# MicroBit_Robot_Interface_RevC.net
KiCad netlist of a schematic drawn in EAGLE
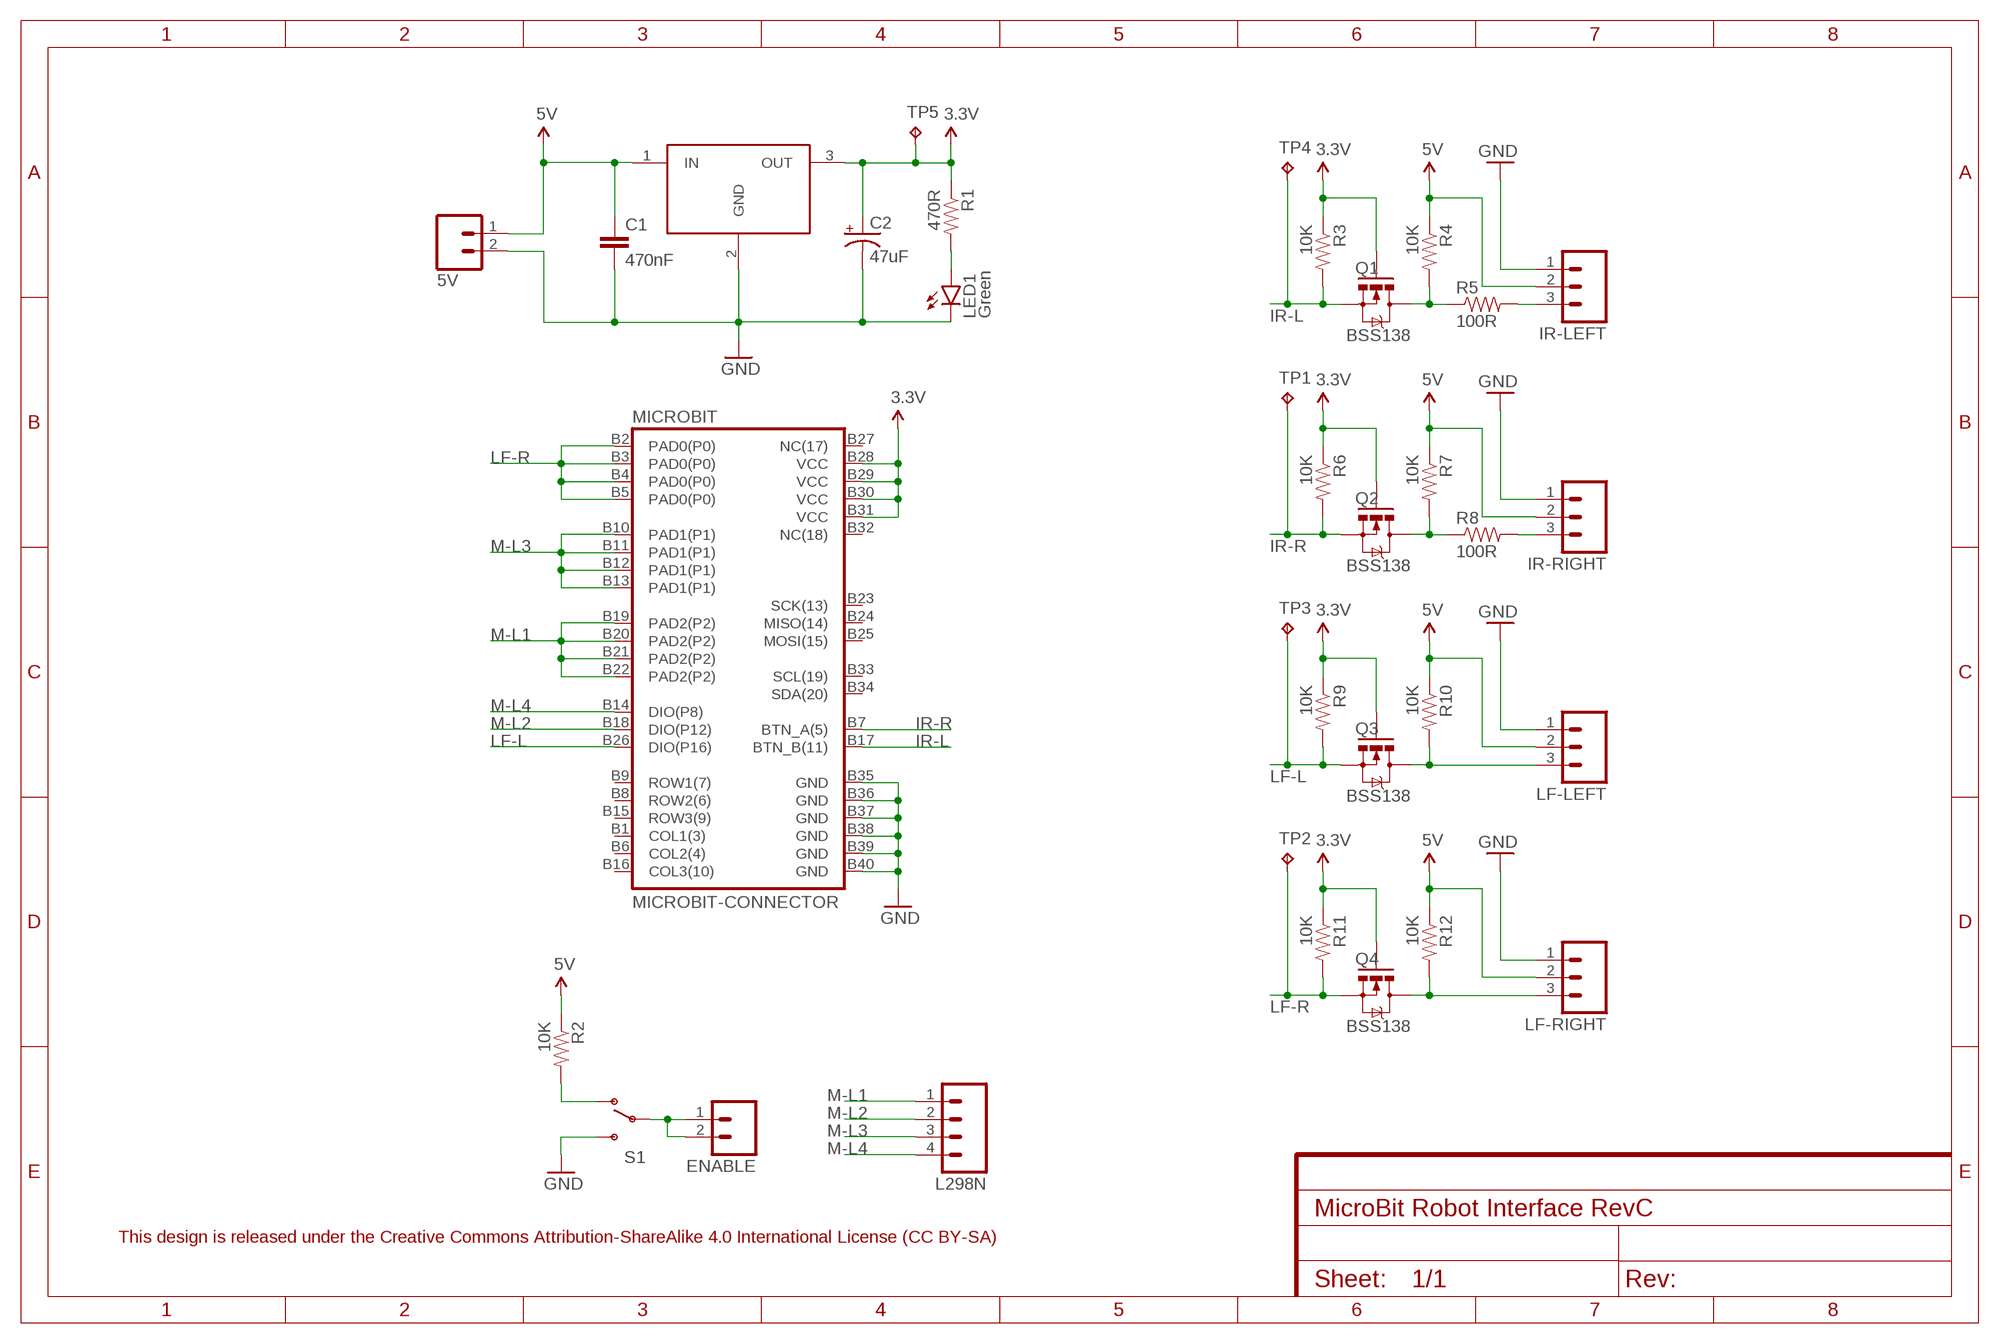
[diagram p0: schematic, sheet 1]

(export (version "E")
  (design (tool "Eeschema 10.0.6"))
  (components
    (comp (ref "5V")
      (value "MCOMP_SCREWTERM_2PIN5MM")
      (footprint "eagle-import:MCOMP-SCREWTERMINAL-5MM-2")
      (libsource (lib "eagle-import") (part "MCOMP_SCREWTERM_2PIN5MM"))
    )
    (comp (ref "C1")
      (value "470nF")
      (footprint "eagle-import:0603-CAP")
      (libsource (lib "eagle-import") (part "CAP0603-CAP"))
    )
    (comp (ref "C2")
      (value "47uF")
      (footprint "eagle-import:CPOL-RADIAL-100UF-25V")
      (libsource (lib "eagle-import") (part "CAP_POLPTH1"))
    )
    (comp (ref "ENABLE")
      (value "M02PTH")
      (footprint "eagle-import:1X02")
      (libsource (lib "eagle-import") (part "M02PTH"))
    )
    (comp (ref "IR-LEFT")
      (value "M03PTH")
      (footprint "eagle-import:1X03")
      (libsource (lib "eagle-import") (part "M03PTH"))
    )
    (comp (ref "IR-RIGHT")
      (value "M03PTH")
      (footprint "eagle-import:1X03")
      (libsource (lib "eagle-import") (part "M03PTH"))
    )
    (comp (ref "L298N")
      (value "M04PTH")
      (footprint "eagle-import:1X04")
      (libsource (lib "eagle-import") (part "M04PTH"))
    )
    (comp (ref "LED1")
      (value "Green")
      (footprint "eagle-import:LED3MM")
      (libsource (lib "eagle-import") (part "LED3MM"))
    )
    (comp (ref "LF-LEFT")
      (value "M03PTH")
      (footprint "eagle-import:1X03")
      (libsource (lib "eagle-import") (part "M03PTH"))
    )
    (comp (ref "LF-RIGHT")
      (value "M03PTH")
      (footprint "eagle-import:1X03")
      (libsource (lib "eagle-import") (part "M03PTH"))
    )
    (comp (ref "MICROBIT")
      (value "MICROBIT-CONNECTOR")
      (footprint "eagle-import:RBB40DHHN_MICROBIT")
      (libsource (lib "eagle-import") (part "MICROBIT-CONNECTOR"))
    )
    (comp (ref "Q1")
      (value "BSS138")
      (footprint "eagle-import:SOT23-3")
      (libsource (lib "eagle-import") (part "MOSFET-NCHANNELBSS138"))
    )
    (comp (ref "Q2")
      (value "BSS138")
      (footprint "eagle-import:SOT23-3")
      (libsource (lib "eagle-import") (part "MOSFET-NCHANNELBSS138"))
    )
    (comp (ref "Q3")
      (value "BSS138")
      (footprint "eagle-import:SOT23-3")
      (libsource (lib "eagle-import") (part "MOSFET-NCHANNELBSS138"))
    )
    (comp (ref "Q4")
      (value "BSS138")
      (footprint "eagle-import:SOT23-3")
      (libsource (lib "eagle-import") (part "MOSFET-NCHANNELBSS138"))
    )
    (comp (ref "R1")
      (value "470R")
      (footprint "eagle-import:0603-RES")
      (libsource (lib "eagle-import") (part "RESISTOR0603-RES"))
    )
    (comp (ref "R2")
      (value "10K")
      (footprint "eagle-import:0603-RES")
      (libsource (lib "eagle-import") (part "RESISTOR0603-RES"))
    )
    (comp (ref "R3")
      (value "10K")
      (footprint "eagle-import:0603-RES")
      (libsource (lib "eagle-import") (part "RESISTOR0603-RES"))
    )
    (comp (ref "R4")
      (value "10K")
      (footprint "eagle-import:0603-RES")
      (libsource (lib "eagle-import") (part "RESISTOR0603-RES"))
    )
    (comp (ref "R5")
      (value "100R")
      (footprint "eagle-import:0603-RES")
      (libsource (lib "eagle-import") (part "RESISTOR0603-RES"))
    )
    (comp (ref "R6")
      (value "10K")
      (footprint "eagle-import:0603-RES")
      (libsource (lib "eagle-import") (part "RESISTOR0603-RES"))
    )
    (comp (ref "R7")
      (value "10K")
      (footprint "eagle-import:0603-RES")
      (libsource (lib "eagle-import") (part "RESISTOR0603-RES"))
    )
    (comp (ref "R8")
      (value "100R")
      (footprint "eagle-import:0603-RES")
      (libsource (lib "eagle-import") (part "RESISTOR0603-RES"))
    )
    (comp (ref "R9")
      (value "10K")
      (footprint "eagle-import:0603-RES")
      (libsource (lib "eagle-import") (part "RESISTOR0603-RES"))
    )
    (comp (ref "R10")
      (value "10K")
      (footprint "eagle-import:0603-RES")
      (libsource (lib "eagle-import") (part "RESISTOR0603-RES"))
    )
    (comp (ref "R11")
      (value "10K")
      (footprint "eagle-import:0603-RES")
      (libsource (lib "eagle-import") (part "RESISTOR0603-RES"))
    )
    (comp (ref "R12")
      (value "10K")
      (footprint "eagle-import:0603-RES")
      (libsource (lib "eagle-import") (part "RESISTOR0603-RES"))
    )
    (comp (ref "S1")
      (value "KNITTER-SWITCH-MFP106D")
      (footprint "eagle-import:KNITTER-SWITCH-MFP106D")
      (libsource (lib "eagle-import") (part "KNITTER-SWITCH-MFP106D"))
    )
    (comp (ref "TP1")
      (value "TPTP10R")
      (footprint "eagle-import:TP10R")
      (libsource (lib "eagle-import") (part "TPTP10R"))
    )
    (comp (ref "TP2")
      (value "TPTP10R")
      (footprint "eagle-import:TP10R")
      (libsource (lib "eagle-import") (part "TPTP10R"))
    )
    (comp (ref "TP3")
      (value "TPTP10R")
      (footprint "eagle-import:TP10R")
      (libsource (lib "eagle-import") (part "TPTP10R"))
    )
    (comp (ref "TP4")
      (value "TPTP10R")
      (footprint "eagle-import:TP10R")
      (libsource (lib "eagle-import") (part "TPTP10R"))
    )
    (comp (ref "TP5")
      (value "TPTP10R")
      (footprint "eagle-import:TP10R")
      (libsource (lib "eagle-import") (part "TPTP10R"))
    )
    (comp (ref "VR1")
      (value "LM3940IMP-3.3")
      (footprint "eagle-import:SOT223")
      (libsource (lib "eagle-import") (part "LM3940IMP-3.3"))
    )
  )
  (nets
    (net (code "1") (name "/IR-L") (class "Default")
      (node (ref "MICROBIT") (pin "B17") (pinfunction "BTN_B(11)_B17") (pintype "input"))
      (node (ref "Q1") (pin "2") (pinfunction "S_2") (pintype "passive"))
      (node (ref "R3") (pin "2") (pinfunction "2_2") (pintype "passive"))
      (node (ref "TP4") (pin "TP") (pinfunction "TP_TP") (pintype "input"))
    )
    (net (code "2") (name "/IR-R") (class "Default")
      (node (ref "MICROBIT") (pin "B7") (pinfunction "BTN_A(5)_B7") (pintype "input"))
      (node (ref "Q2") (pin "2") (pinfunction "S_2") (pintype "passive"))
      (node (ref "R6") (pin "2") (pinfunction "2_2") (pintype "passive"))
      (node (ref "TP1") (pin "TP") (pinfunction "TP_TP") (pintype "input"))
    )
    (net (code "3") (name "/LF-L") (class "Default")
      (node (ref "MICROBIT") (pin "B26") (pinfunction "DIO(P16)_B26") (pintype "bidirectional"))
      (node (ref "Q3") (pin "2") (pinfunction "S_2") (pintype "passive"))
      (node (ref "R9") (pin "2") (pinfunction "2_2") (pintype "passive"))
      (node (ref "TP3") (pin "TP") (pinfunction "TP_TP") (pintype "input"))
    )
    (net (code "4") (name "/LF-R") (class "Default")
      (node (ref "MICROBIT") (pin "B2") (pinfunction "PAD0(P0)_B2") (pintype "bidirectional"))
      (node (ref "MICROBIT") (pin "B3") (pinfunction "PAD0(P0)_B3") (pintype "bidirectional"))
      (node (ref "MICROBIT") (pin "B4") (pinfunction "PAD0(P0)_B4") (pintype "bidirectional"))
      (node (ref "MICROBIT") (pin "B5") (pinfunction "PAD0(P0)_B5") (pintype "bidirectional"))
      (node (ref "Q4") (pin "2") (pinfunction "S_2") (pintype "passive"))
      (node (ref "R11") (pin "2") (pinfunction "2_2") (pintype "passive"))
      (node (ref "TP2") (pin "TP") (pinfunction "TP_TP") (pintype "input"))
    )
    (net (code "5") (name "/M-L1") (class "Default")
      (node (ref "L298N") (pin "1") (pinfunction "1_1") (pintype "passive"))
      (node (ref "MICROBIT") (pin "B19") (pinfunction "PAD2(P2)_B19") (pintype "bidirectional"))
      (node (ref "MICROBIT") (pin "B20") (pinfunction "PAD2(P2)_B20") (pintype "bidirectional"))
      (node (ref "MICROBIT") (pin "B21") (pinfunction "PAD2(P2)_B21") (pintype "bidirectional"))
      (node (ref "MICROBIT") (pin "B22") (pinfunction "PAD2(P2)_B22") (pintype "bidirectional"))
    )
    (net (code "6") (name "/M-L2") (class "Default")
      (node (ref "L298N") (pin "2") (pinfunction "2_2") (pintype "passive"))
      (node (ref "MICROBIT") (pin "B18") (pinfunction "DIO(P12)_B18") (pintype "bidirectional"))
    )
    (net (code "7") (name "/M-L3") (class "Default")
      (node (ref "L298N") (pin "3") (pinfunction "3_3") (pintype "passive"))
      (node (ref "MICROBIT") (pin "B10") (pinfunction "PAD1(P1)_B10") (pintype "bidirectional"))
      (node (ref "MICROBIT") (pin "B11") (pinfunction "PAD1(P1)_B11") (pintype "bidirectional"))
      (node (ref "MICROBIT") (pin "B12") (pinfunction "PAD1(P1)_B12") (pintype "bidirectional"))
      (node (ref "MICROBIT") (pin "B13") (pinfunction "PAD1(P1)_B13") (pintype "bidirectional"))
    )
    (net (code "8") (name "/M-L4") (class "Default")
      (node (ref "L298N") (pin "4") (pinfunction "4_4") (pintype "passive"))
      (node (ref "MICROBIT") (pin "B14") (pinfunction "DIO(P8)_B14") (pintype "bidirectional"))
    )
    (net (code "9") (name "3.3V") (class "Default")
      (node (ref "C2") (pin "1") (pinfunction "+_1") (pintype "passive"))
      (node (ref "MICROBIT") (pin "B28") (pinfunction "VCC_B28") (pintype "power_in"))
      (node (ref "MICROBIT") (pin "B29") (pinfunction "VCC_B29") (pintype "power_in"))
      (node (ref "MICROBIT") (pin "B30") (pinfunction "VCC_B30") (pintype "power_in"))
      (node (ref "MICROBIT") (pin "B31") (pinfunction "VCC_B31") (pintype "power_in"))
      (node (ref "Q1") (pin "1") (pinfunction "G_1") (pintype "passive"))
      (node (ref "Q2") (pin "1") (pinfunction "G_1") (pintype "passive"))
      (node (ref "Q3") (pin "1") (pinfunction "G_1") (pintype "passive"))
      (node (ref "Q4") (pin "1") (pinfunction "G_1") (pintype "passive"))
      (node (ref "R1") (pin "1") (pinfunction "1_1") (pintype "passive"))
      (node (ref "R11") (pin "1") (pinfunction "1_1") (pintype "passive"))
      (node (ref "R3") (pin "1") (pinfunction "1_1") (pintype "passive"))
      (node (ref "R6") (pin "1") (pinfunction "1_1") (pintype "passive"))
      (node (ref "R9") (pin "1") (pinfunction "1_1") (pintype "passive"))
      (node (ref "TP5") (pin "TP") (pinfunction "TP_TP") (pintype "input"))
      (node (ref "VR1") (pin "3") (pinfunction "OUT_3") (pintype "power_in"))
    )
    (net (code "10") (name "5V") (class "Default")
      (node (ref "5V") (pin "1") (pinfunction "1_1") (pintype "passive"))
      (node (ref "C1") (pin "1") (pinfunction "1_1") (pintype "passive"))
      (node (ref "IR-LEFT") (pin "2") (pinfunction "2_2") (pintype "passive"))
      (node (ref "IR-RIGHT") (pin "2") (pinfunction "2_2") (pintype "passive"))
      (node (ref "LF-LEFT") (pin "2") (pinfunction "2_2") (pintype "passive"))
      (node (ref "LF-RIGHT") (pin "2") (pinfunction "2_2") (pintype "passive"))
      (node (ref "R10") (pin "1") (pinfunction "1_1") (pintype "passive"))
      (node (ref "R12") (pin "1") (pinfunction "1_1") (pintype "passive"))
      (node (ref "R2") (pin "1") (pinfunction "1_1") (pintype "passive"))
      (node (ref "R4") (pin "1") (pinfunction "1_1") (pintype "passive"))
      (node (ref "R7") (pin "1") (pinfunction "1_1") (pintype "passive"))
      (node (ref "VR1") (pin "1") (pinfunction "IN_1") (pintype "power_in"))
    )
    (net (code "11") (name "GND") (class "Default")
      (node (ref "5V") (pin "2") (pinfunction "2_2") (pintype "passive"))
      (node (ref "C1") (pin "2") (pinfunction "2_2") (pintype "passive"))
      (node (ref "C2") (pin "2") (pinfunction "-_2") (pintype "passive"))
      (node (ref "IR-LEFT") (pin "1") (pinfunction "1_1") (pintype "passive"))
      (node (ref "IR-RIGHT") (pin "1") (pinfunction "1_1") (pintype "passive"))
      (node (ref "LED1") (pin "K") (pinfunction "C_K") (pintype "passive"))
      (node (ref "LF-LEFT") (pin "1") (pinfunction "1_1") (pintype "passive"))
      (node (ref "LF-RIGHT") (pin "1") (pinfunction "1_1") (pintype "passive"))
      (node (ref "MICROBIT") (pin "B35") (pinfunction "GND_B35") (pintype "power_in"))
      (node (ref "MICROBIT") (pin "B36") (pinfunction "GND_B36") (pintype "power_in"))
      (node (ref "MICROBIT") (pin "B37") (pinfunction "GND_B37") (pintype "power_in"))
      (node (ref "MICROBIT") (pin "B38") (pinfunction "GND_B38") (pintype "power_in"))
      (node (ref "MICROBIT") (pin "B39") (pinfunction "GND_B39") (pintype "power_in"))
      (node (ref "MICROBIT") (pin "B40") (pinfunction "GND_B40") (pintype "power_in"))
      (node (ref "S1") (pin "P$2") (pinfunction "POS2_P$2") (pintype "passive"))
      (node (ref "VR1") (pin "2") (pinfunction "GND_2") (pintype "power_in"))
    )
    (net (code "12") (name "Net-(IR-LEFT-Pad3)") (class "Default")
      (node (ref "IR-LEFT") (pin "3") (pinfunction "3_3") (pintype "passive"))
      (node (ref "R5") (pin "2") (pinfunction "2_2") (pintype "passive"))
    )
    (net (code "13") (name "Net-(IR-RIGHT-Pad3)") (class "Default")
      (node (ref "IR-RIGHT") (pin "3") (pinfunction "3_3") (pintype "passive"))
      (node (ref "R8") (pin "2") (pinfunction "2_2") (pintype "passive"))
    )
    (net (code "14") (name "Net-(LED1-PadA)") (class "Default")
      (node (ref "LED1") (pin "A") (pinfunction "A_A") (pintype "passive"))
      (node (ref "R1") (pin "2") (pinfunction "2_2") (pintype "passive"))
    )
    (net (code "15") (name "Net-(Q1-D)") (class "Default")
      (node (ref "Q1") (pin "3") (pinfunction "D_3") (pintype "passive"))
      (node (ref "R4") (pin "2") (pinfunction "2_2") (pintype "passive"))
      (node (ref "R5") (pin "1") (pinfunction "1_1") (pintype "passive"))
    )
    (net (code "16") (name "Net-(Q2-D)") (class "Default")
      (node (ref "Q2") (pin "3") (pinfunction "D_3") (pintype "passive"))
      (node (ref "R7") (pin "2") (pinfunction "2_2") (pintype "passive"))
      (node (ref "R8") (pin "1") (pinfunction "1_1") (pintype "passive"))
    )
    (net (code "17") (name "Net-(Q3-D)") (class "Default")
      (node (ref "LF-LEFT") (pin "3") (pinfunction "3_3") (pintype "passive"))
      (node (ref "Q3") (pin "3") (pinfunction "D_3") (pintype "passive"))
      (node (ref "R10") (pin "2") (pinfunction "2_2") (pintype "passive"))
    )
    (net (code "18") (name "Net-(Q4-D)") (class "Default")
      (node (ref "LF-RIGHT") (pin "3") (pinfunction "3_3") (pintype "passive"))
      (node (ref "Q4") (pin "3") (pinfunction "D_3") (pintype "passive"))
      (node (ref "R12") (pin "2") (pinfunction "2_2") (pintype "passive"))
    )
    (net (code "19") (name "Net-(S1-COMMON)") (class "Default")
      (node (ref "ENABLE") (pin "1") (pinfunction "1_1") (pintype "passive"))
      (node (ref "ENABLE") (pin "2") (pinfunction "2_2") (pintype "passive"))
      (node (ref "S1") (pin "WIPER") (pinfunction "COMMON_WIPER") (pintype "passive"))
    )
    (net (code "20") (name "Net-(S1-POS1)") (class "Default")
      (node (ref "R2") (pin "2") (pinfunction "2_2") (pintype "passive"))
      (node (ref "S1") (pin "P$1") (pinfunction "POS1_P$1") (pintype "passive"))
    )
    (net (code "21") (name "unconnected-(MICROBIT-COL1(3)-PadB1)") (class "Default")
      (node (ref "MICROBIT") (pin "B1") (pinfunction "COL1(3)_B1") (pintype "output"))
    )
    (net (code "22") (name "unconnected-(MICROBIT-COL2(4)-PadB6)") (class "Default")
      (node (ref "MICROBIT") (pin "B6") (pinfunction "COL2(4)_B6") (pintype "output"))
    )
    (net (code "23") (name "unconnected-(MICROBIT-COL3(10)-PadB16)") (class "Default")
      (node (ref "MICROBIT") (pin "B16") (pinfunction "COL3(10)_B16") (pintype "output"))
    )
    (net (code "24") (name "unconnected-(MICROBIT-MISO(14)-PadB24)") (class "Default")
      (node (ref "MICROBIT") (pin "B24") (pinfunction "MISO(14)_B24") (pintype "bidirectional"))
    )
    (net (code "25") (name "unconnected-(MICROBIT-MOSI(15)-PadB25)") (class "Default")
      (node (ref "MICROBIT") (pin "B25") (pinfunction "MOSI(15)_B25") (pintype "bidirectional"))
    )
    (net (code "26") (name "unconnected-(MICROBIT-NC(17)-PadB27)") (class "Default")
      (node (ref "MICROBIT") (pin "B27") (pinfunction "NC(17)_B27") (pintype "no_connect"))
    )
    (net (code "27") (name "unconnected-(MICROBIT-NC(18)-PadB32)") (class "Default")
      (node (ref "MICROBIT") (pin "B32") (pinfunction "NC(18)_B32") (pintype "no_connect"))
    )
    (net (code "28") (name "unconnected-(MICROBIT-ROW1(7)-PadB9)") (class "Default")
      (node (ref "MICROBIT") (pin "B9") (pinfunction "ROW1(7)_B9") (pintype "output"))
    )
    (net (code "29") (name "unconnected-(MICROBIT-ROW2(6)-PadB8)") (class "Default")
      (node (ref "MICROBIT") (pin "B8") (pinfunction "ROW2(6)_B8") (pintype "output"))
    )
    (net (code "30") (name "unconnected-(MICROBIT-ROW3(9)-PadB15)") (class "Default")
      (node (ref "MICROBIT") (pin "B15") (pinfunction "ROW3(9)_B15") (pintype "output"))
    )
    (net (code "31") (name "unconnected-(MICROBIT-SCK(13)-PadB23)") (class "Default")
      (node (ref "MICROBIT") (pin "B23") (pinfunction "SCK(13)_B23") (pintype "bidirectional"))
    )
    (net (code "32") (name "unconnected-(MICROBIT-SCL(19)-PadB33)") (class "Default")
      (node (ref "MICROBIT") (pin "B33") (pinfunction "SCL(19)_B33") (pintype "bidirectional"))
    )
    (net (code "33") (name "unconnected-(MICROBIT-SDA(20)-PadB34)") (class "Default")
      (node (ref "MICROBIT") (pin "B34") (pinfunction "SDA(20)_B34") (pintype "bidirectional"))
    )
  )
)
